# Haptic_Sleeve_Schematic.net
KiCad netlist of a schematic drawn in EAGLE
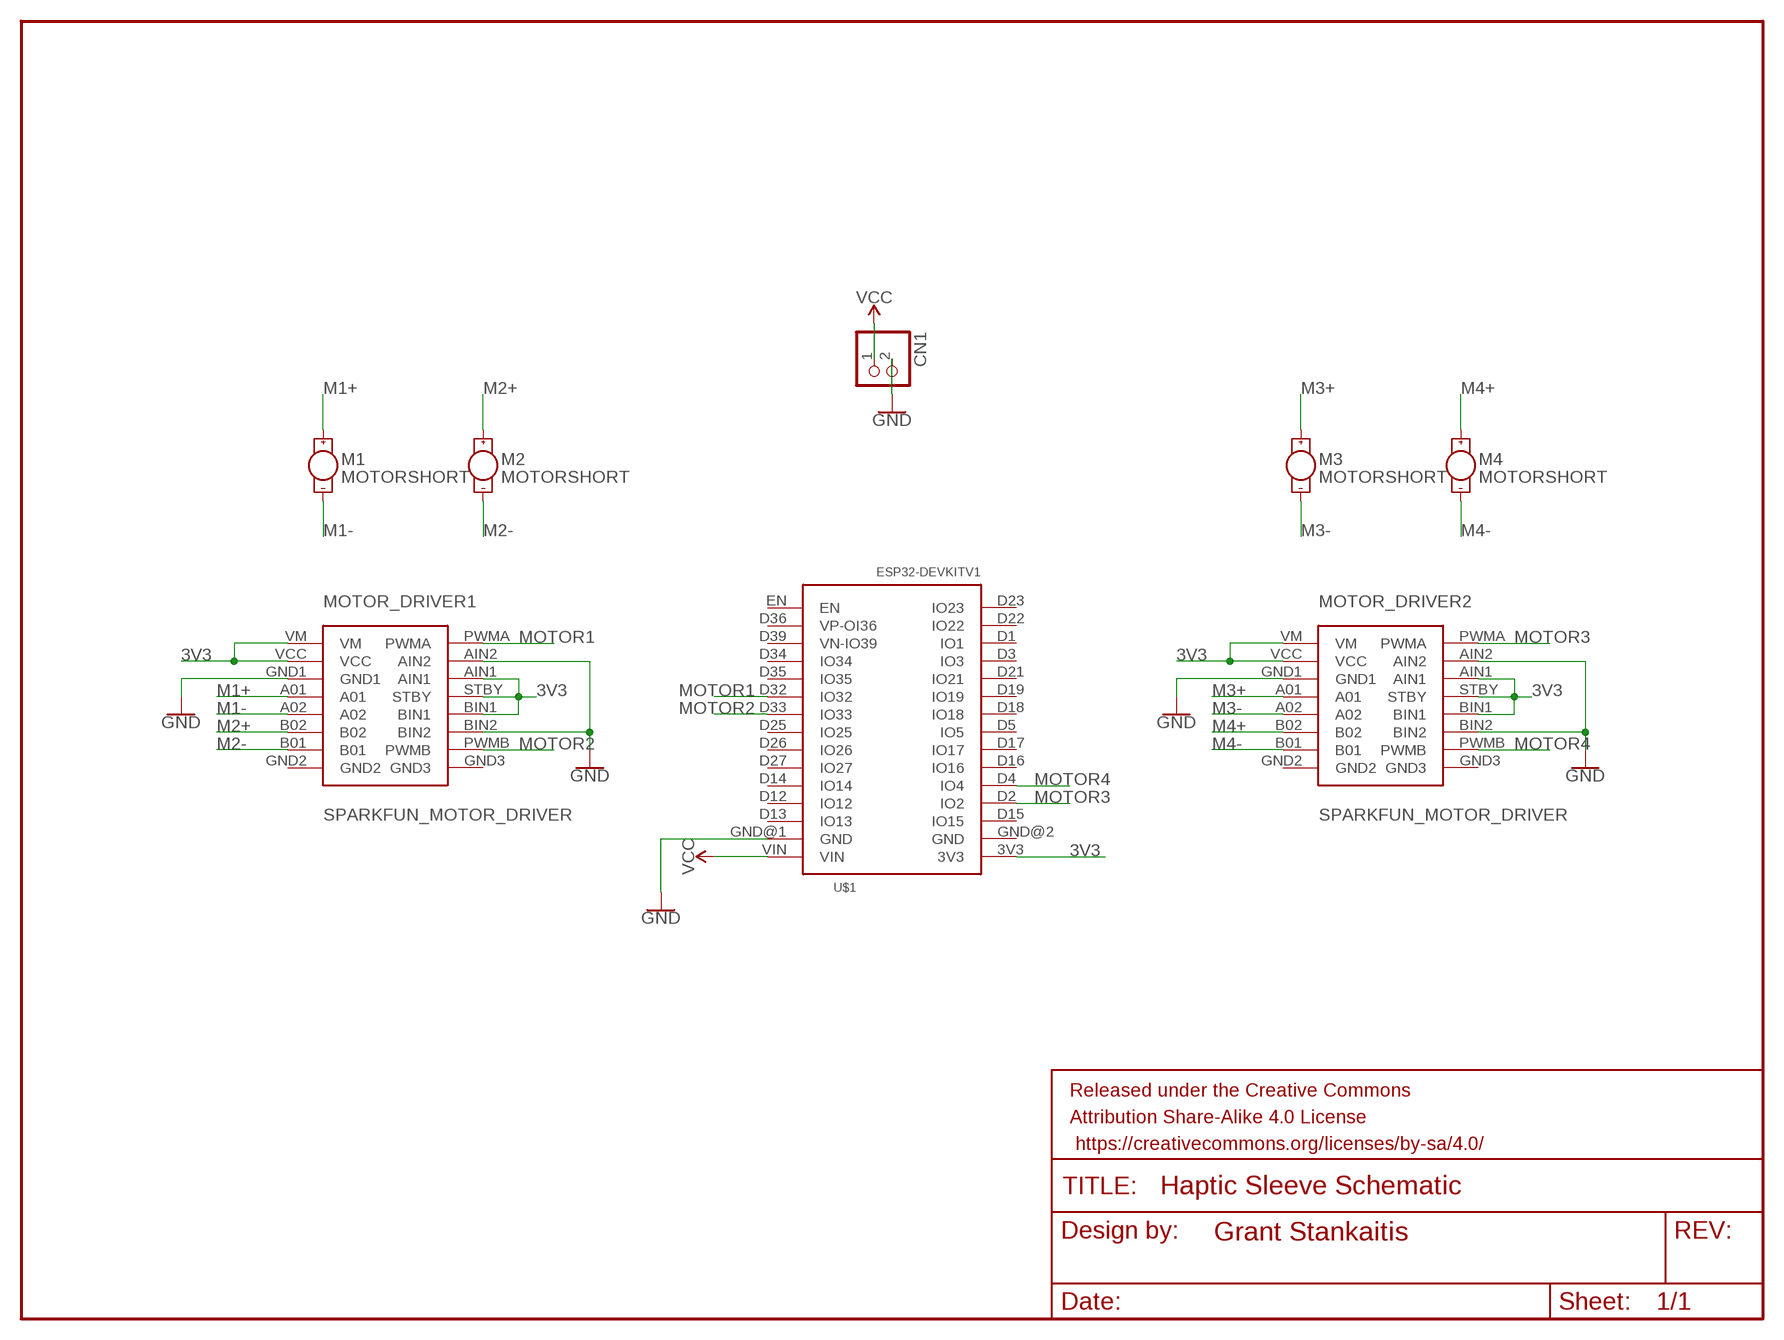
[diagram p0: schematic, sheet 1]

(export (version "E")
  (design (tool "Eeschema 10.0.6"))
  (components
    (comp (ref "CN1")
      (value "JST_2PIN-THM-RA")
      (footprint "eagle-import:JST-PH-2-THM-RA")
      (libsource (lib "eagle-import") (part "JST_2PIN-THM-RA"))
    )
    (comp (ref "FRAME1")
      (value "FRAME-LETTERNO_PACKAGE")
      (footprint "eagle-import:DUMMY")
      (fields (field (name "DESIGNER") "Nobody") (field (name "DESIGNER_1") "Grant Stankaitis"))
      (libsource (lib "eagle-import") (part "FRAME-LETTERNO_PACKAGE"))
    )
    (comp (ref "M1")
      (value "MOTORSHORT")
      (footprint "eagle-import:VIBE-MOTOR-10MM-SMD")
      (libsource (lib "eagle-import") (part "MOTORSHORT"))
    )
    (comp (ref "M2")
      (value "MOTORSHORT")
      (footprint "eagle-import:VIBE-MOTOR-10MM-SMD")
      (libsource (lib "eagle-import") (part "MOTORSHORT"))
    )
    (comp (ref "M3")
      (value "MOTORSHORT")
      (footprint "eagle-import:VIBE-MOTOR-10MM-SMD")
      (libsource (lib "eagle-import") (part "MOTORSHORT"))
    )
    (comp (ref "M4")
      (value "MOTORSHORT")
      (footprint "eagle-import:VIBE-MOTOR-10MM-SMD")
      (libsource (lib "eagle-import") (part "MOTORSHORT"))
    )
    (comp (ref "MOTOR_DRIVER1")
      (value "SPARKFUN_MOTOR_DRIVER")
      (footprint "eagle-import:SPARKFUN_MOTOR_DRIVER")
      (libsource (lib "eagle-import") (part "SPARKFUN_MOTOR_DRIVER"))
    )
    (comp (ref "MOTOR_DRIVER2")
      (value "SPARKFUN_MOTOR_DRIVER")
      (footprint "eagle-import:SPARKFUN_MOTOR_DRIVER")
      (libsource (lib "eagle-import") (part "SPARKFUN_MOTOR_DRIVER"))
    )
    (comp (ref "U$1")
      (value "ESP32DEVKITV1")
      (footprint "eagle-import:ESP32-DEVKITV1")
      (libsource (lib "eagle-import") (part "ESP32DEVKITV1"))
    )
  )
  (nets
    (net (code "1") (name "/3V3") (class "Default")
      (node (ref "MOTOR_DRIVER1") (pin "AIN1") (pinfunction "AIN1_AIN1") (pintype "bidirectional"))
      (node (ref "MOTOR_DRIVER1") (pin "BIN1") (pinfunction "BIN1_BIN1") (pintype "bidirectional"))
      (node (ref "MOTOR_DRIVER1") (pin "STBY") (pinfunction "STBY_STBY") (pintype "bidirectional"))
      (node (ref "MOTOR_DRIVER1") (pin "VCC") (pinfunction "VCC_VCC") (pintype "bidirectional"))
      (node (ref "MOTOR_DRIVER1") (pin "VM") (pinfunction "VM_VM") (pintype "bidirectional"))
      (node (ref "MOTOR_DRIVER2") (pin "AIN1") (pinfunction "AIN1_AIN1") (pintype "bidirectional"))
      (node (ref "MOTOR_DRIVER2") (pin "BIN1") (pinfunction "BIN1_BIN1") (pintype "bidirectional"))
      (node (ref "MOTOR_DRIVER2") (pin "STBY") (pinfunction "STBY_STBY") (pintype "bidirectional"))
      (node (ref "MOTOR_DRIVER2") (pin "VCC") (pinfunction "VCC_VCC") (pintype "bidirectional"))
      (node (ref "MOTOR_DRIVER2") (pin "VM") (pinfunction "VM_VM") (pintype "bidirectional"))
      (node (ref "U$1") (pin "3V3") (pinfunction "3V3_3V3") (pintype "bidirectional"))
    )
    (net (code "2") (name "/M1+") (class "Default")
      (node (ref "M1") (pin "+") (pinfunction "+_+") (pintype "bidirectional"))
      (node (ref "MOTOR_DRIVER1") (pin "A01") (pinfunction "A01_A01") (pintype "bidirectional"))
    )
    (net (code "3") (name "/M1-") (class "Default")
      (node (ref "M1") (pin "-") (pinfunction "-_-") (pintype "bidirectional"))
      (node (ref "MOTOR_DRIVER1") (pin "A02") (pinfunction "A02_A02") (pintype "bidirectional"))
    )
    (net (code "4") (name "/M2+") (class "Default")
      (node (ref "M2") (pin "+") (pinfunction "+_+") (pintype "bidirectional"))
      (node (ref "MOTOR_DRIVER1") (pin "B02") (pinfunction "B02_B02") (pintype "bidirectional"))
    )
    (net (code "5") (name "/M2-") (class "Default")
      (node (ref "M2") (pin "-") (pinfunction "-_-") (pintype "bidirectional"))
      (node (ref "MOTOR_DRIVER1") (pin "B01") (pinfunction "B01_B01") (pintype "bidirectional"))
    )
    (net (code "6") (name "/M3+") (class "Default")
      (node (ref "M3") (pin "+") (pinfunction "+_+") (pintype "bidirectional"))
      (node (ref "MOTOR_DRIVER2") (pin "A01") (pinfunction "A01_A01") (pintype "bidirectional"))
    )
    (net (code "7") (name "/M3-") (class "Default")
      (node (ref "M3") (pin "-") (pinfunction "-_-") (pintype "bidirectional"))
      (node (ref "MOTOR_DRIVER2") (pin "A02") (pinfunction "A02_A02") (pintype "bidirectional"))
    )
    (net (code "8") (name "/M4+") (class "Default")
      (node (ref "M4") (pin "+") (pinfunction "+_+") (pintype "bidirectional"))
      (node (ref "MOTOR_DRIVER2") (pin "B02") (pinfunction "B02_B02") (pintype "bidirectional"))
    )
    (net (code "9") (name "/M4-") (class "Default")
      (node (ref "M4") (pin "-") (pinfunction "-_-") (pintype "bidirectional"))
      (node (ref "MOTOR_DRIVER2") (pin "B01") (pinfunction "B01_B01") (pintype "bidirectional"))
    )
    (net (code "10") (name "/MOTOR1") (class "Default")
      (node (ref "MOTOR_DRIVER1") (pin "PWMA") (pinfunction "PWMA_PWMA") (pintype "bidirectional"))
      (node (ref "U$1") (pin "D32") (pinfunction "IO32_D32") (pintype "bidirectional"))
    )
    (net (code "11") (name "/MOTOR2") (class "Default")
      (node (ref "MOTOR_DRIVER1") (pin "PWMB") (pinfunction "PWMB_PWMB") (pintype "bidirectional"))
      (node (ref "U$1") (pin "D33") (pinfunction "IO33_D33") (pintype "bidirectional"))
    )
    (net (code "12") (name "/MOTOR3") (class "Default")
      (node (ref "MOTOR_DRIVER2") (pin "PWMA") (pinfunction "PWMA_PWMA") (pintype "bidirectional"))
      (node (ref "U$1") (pin "D2") (pinfunction "IO2_D2") (pintype "bidirectional"))
    )
    (net (code "13") (name "/MOTOR4") (class "Default")
      (node (ref "MOTOR_DRIVER2") (pin "PWMB") (pinfunction "PWMB_PWMB") (pintype "bidirectional"))
      (node (ref "U$1") (pin "D4") (pinfunction "IO4_D4") (pintype "bidirectional"))
    )
    (net (code "14") (name "GND") (class "Default")
      (node (ref "CN1") (pin "2") (pinfunction "1_2") (pintype "passive"))
      (node (ref "MOTOR_DRIVER1") (pin "AIN2") (pinfunction "AIN2_AIN2") (pintype "bidirectional"))
      (node (ref "MOTOR_DRIVER1") (pin "BIN2") (pinfunction "BIN2_BIN2") (pintype "bidirectional"))
      (node (ref "MOTOR_DRIVER1") (pin "GND1") (pinfunction "GND1_GND1") (pintype "bidirectional"))
      (node (ref "MOTOR_DRIVER2") (pin "AIN2") (pinfunction "AIN2_AIN2") (pintype "bidirectional"))
      (node (ref "MOTOR_DRIVER2") (pin "BIN2") (pinfunction "BIN2_BIN2") (pintype "bidirectional"))
      (node (ref "MOTOR_DRIVER2") (pin "GND1") (pinfunction "GND1_GND1") (pintype "bidirectional"))
      (node (ref "U$1") (pin "GND@1") (pinfunction "GND_GND@1") (pintype "bidirectional"))
    )
    (net (code "15") (name "VCC") (class "Default")
      (node (ref "CN1") (pin "1") (pinfunction "2_1") (pintype "passive"))
      (node (ref "U$1") (pin "VIN") (pinfunction "VIN_VIN") (pintype "bidirectional"))
    )
    (net (code "16") (name "unconnected-(MOTOR_DRIVER1-PadGND2)") (class "Default")
      (node (ref "MOTOR_DRIVER1") (pin "GND2") (pinfunction "GND2_GND2") (pintype "bidirectional"))
    )
    (net (code "17") (name "unconnected-(MOTOR_DRIVER1-PadGND3)") (class "Default")
      (node (ref "MOTOR_DRIVER1") (pin "GND3") (pinfunction "GND3_GND3") (pintype "bidirectional"))
    )
    (net (code "18") (name "unconnected-(MOTOR_DRIVER2-PadGND2)") (class "Default")
      (node (ref "MOTOR_DRIVER2") (pin "GND2") (pinfunction "GND2_GND2") (pintype "bidirectional"))
    )
    (net (code "19") (name "unconnected-(MOTOR_DRIVER2-PadGND3)") (class "Default")
      (node (ref "MOTOR_DRIVER2") (pin "GND3") (pinfunction "GND3_GND3") (pintype "bidirectional"))
    )
    (net (code "20") (name "unconnected-(U$1-GND-PadGND@2)") (class "Default")
      (node (ref "U$1") (pin "GND@2") (pinfunction "GND_GND@2") (pintype "bidirectional"))
    )
    (net (code "21") (name "unconnected-(U$1-IO1-PadD1)") (class "Default")
      (node (ref "U$1") (pin "D1") (pinfunction "IO1_D1") (pintype "bidirectional"))
    )
    (net (code "22") (name "unconnected-(U$1-IO3-PadD3)") (class "Default")
      (node (ref "U$1") (pin "D3") (pinfunction "IO3_D3") (pintype "bidirectional"))
    )
    (net (code "23") (name "unconnected-(U$1-IO5-PadD5)") (class "Default")
      (node (ref "U$1") (pin "D5") (pinfunction "IO5_D5") (pintype "bidirectional"))
    )
    (net (code "24") (name "unconnected-(U$1-IO12-PadD12)") (class "Default")
      (node (ref "U$1") (pin "D12") (pinfunction "IO12_D12") (pintype "bidirectional"))
    )
    (net (code "25") (name "unconnected-(U$1-IO13-PadD13)") (class "Default")
      (node (ref "U$1") (pin "D13") (pinfunction "IO13_D13") (pintype "bidirectional"))
    )
    (net (code "26") (name "unconnected-(U$1-IO14-PadD14)") (class "Default")
      (node (ref "U$1") (pin "D14") (pinfunction "IO14_D14") (pintype "bidirectional"))
    )
    (net (code "27") (name "unconnected-(U$1-IO15-PadD15)") (class "Default")
      (node (ref "U$1") (pin "D15") (pinfunction "IO15_D15") (pintype "bidirectional"))
    )
    (net (code "28") (name "unconnected-(U$1-IO16-PadD16)") (class "Default")
      (node (ref "U$1") (pin "D16") (pinfunction "IO16_D16") (pintype "bidirectional"))
    )
    (net (code "29") (name "unconnected-(U$1-IO17-PadD17)") (class "Default")
      (node (ref "U$1") (pin "D17") (pinfunction "IO17_D17") (pintype "bidirectional"))
    )
    (net (code "30") (name "unconnected-(U$1-IO18-PadD18)") (class "Default")
      (node (ref "U$1") (pin "D18") (pinfunction "IO18_D18") (pintype "bidirectional"))
    )
    (net (code "31") (name "unconnected-(U$1-IO19-PadD19)") (class "Default")
      (node (ref "U$1") (pin "D19") (pinfunction "IO19_D19") (pintype "bidirectional"))
    )
    (net (code "32") (name "unconnected-(U$1-IO21-PadD21)") (class "Default")
      (node (ref "U$1") (pin "D21") (pinfunction "IO21_D21") (pintype "bidirectional"))
    )
    (net (code "33") (name "unconnected-(U$1-IO22-PadD22)") (class "Default")
      (node (ref "U$1") (pin "D22") (pinfunction "IO22_D22") (pintype "bidirectional"))
    )
    (net (code "34") (name "unconnected-(U$1-IO23-PadD23)") (class "Default")
      (node (ref "U$1") (pin "D23") (pinfunction "IO23_D23") (pintype "bidirectional"))
    )
    (net (code "35") (name "unconnected-(U$1-IO25-PadD25)") (class "Default")
      (node (ref "U$1") (pin "D25") (pinfunction "IO25_D25") (pintype "bidirectional"))
    )
    (net (code "36") (name "unconnected-(U$1-IO26-PadD26)") (class "Default")
      (node (ref "U$1") (pin "D26") (pinfunction "IO26_D26") (pintype "bidirectional"))
    )
    (net (code "37") (name "unconnected-(U$1-IO27-PadD27)") (class "Default")
      (node (ref "U$1") (pin "D27") (pinfunction "IO27_D27") (pintype "bidirectional"))
    )
    (net (code "38") (name "unconnected-(U$1-IO34-PadD34)") (class "Default")
      (node (ref "U$1") (pin "D34") (pinfunction "IO34_D34") (pintype "bidirectional"))
    )
    (net (code "39") (name "unconnected-(U$1-IO35-PadD35)") (class "Default")
      (node (ref "U$1") (pin "D35") (pinfunction "IO35_D35") (pintype "bidirectional"))
    )
    (net (code "40") (name "unconnected-(U$1-PadEN)") (class "Default")
      (node (ref "U$1") (pin "EN") (pinfunction "EN_EN") (pintype "bidirectional"))
    )
    (net (code "41") (name "unconnected-(U$1-VN-IO39-PadD39)") (class "Default")
      (node (ref "U$1") (pin "D39") (pinfunction "VN-IO39_D39") (pintype "bidirectional"))
    )
    (net (code "42") (name "unconnected-(U$1-VP-OI36-PadD36)") (class "Default")
      (node (ref "U$1") (pin "D36") (pinfunction "VP-OI36_D36") (pintype "bidirectional"))
    )
  )
)
